# main.net
KiCad netlist of a schematic drawn in Altium Designer
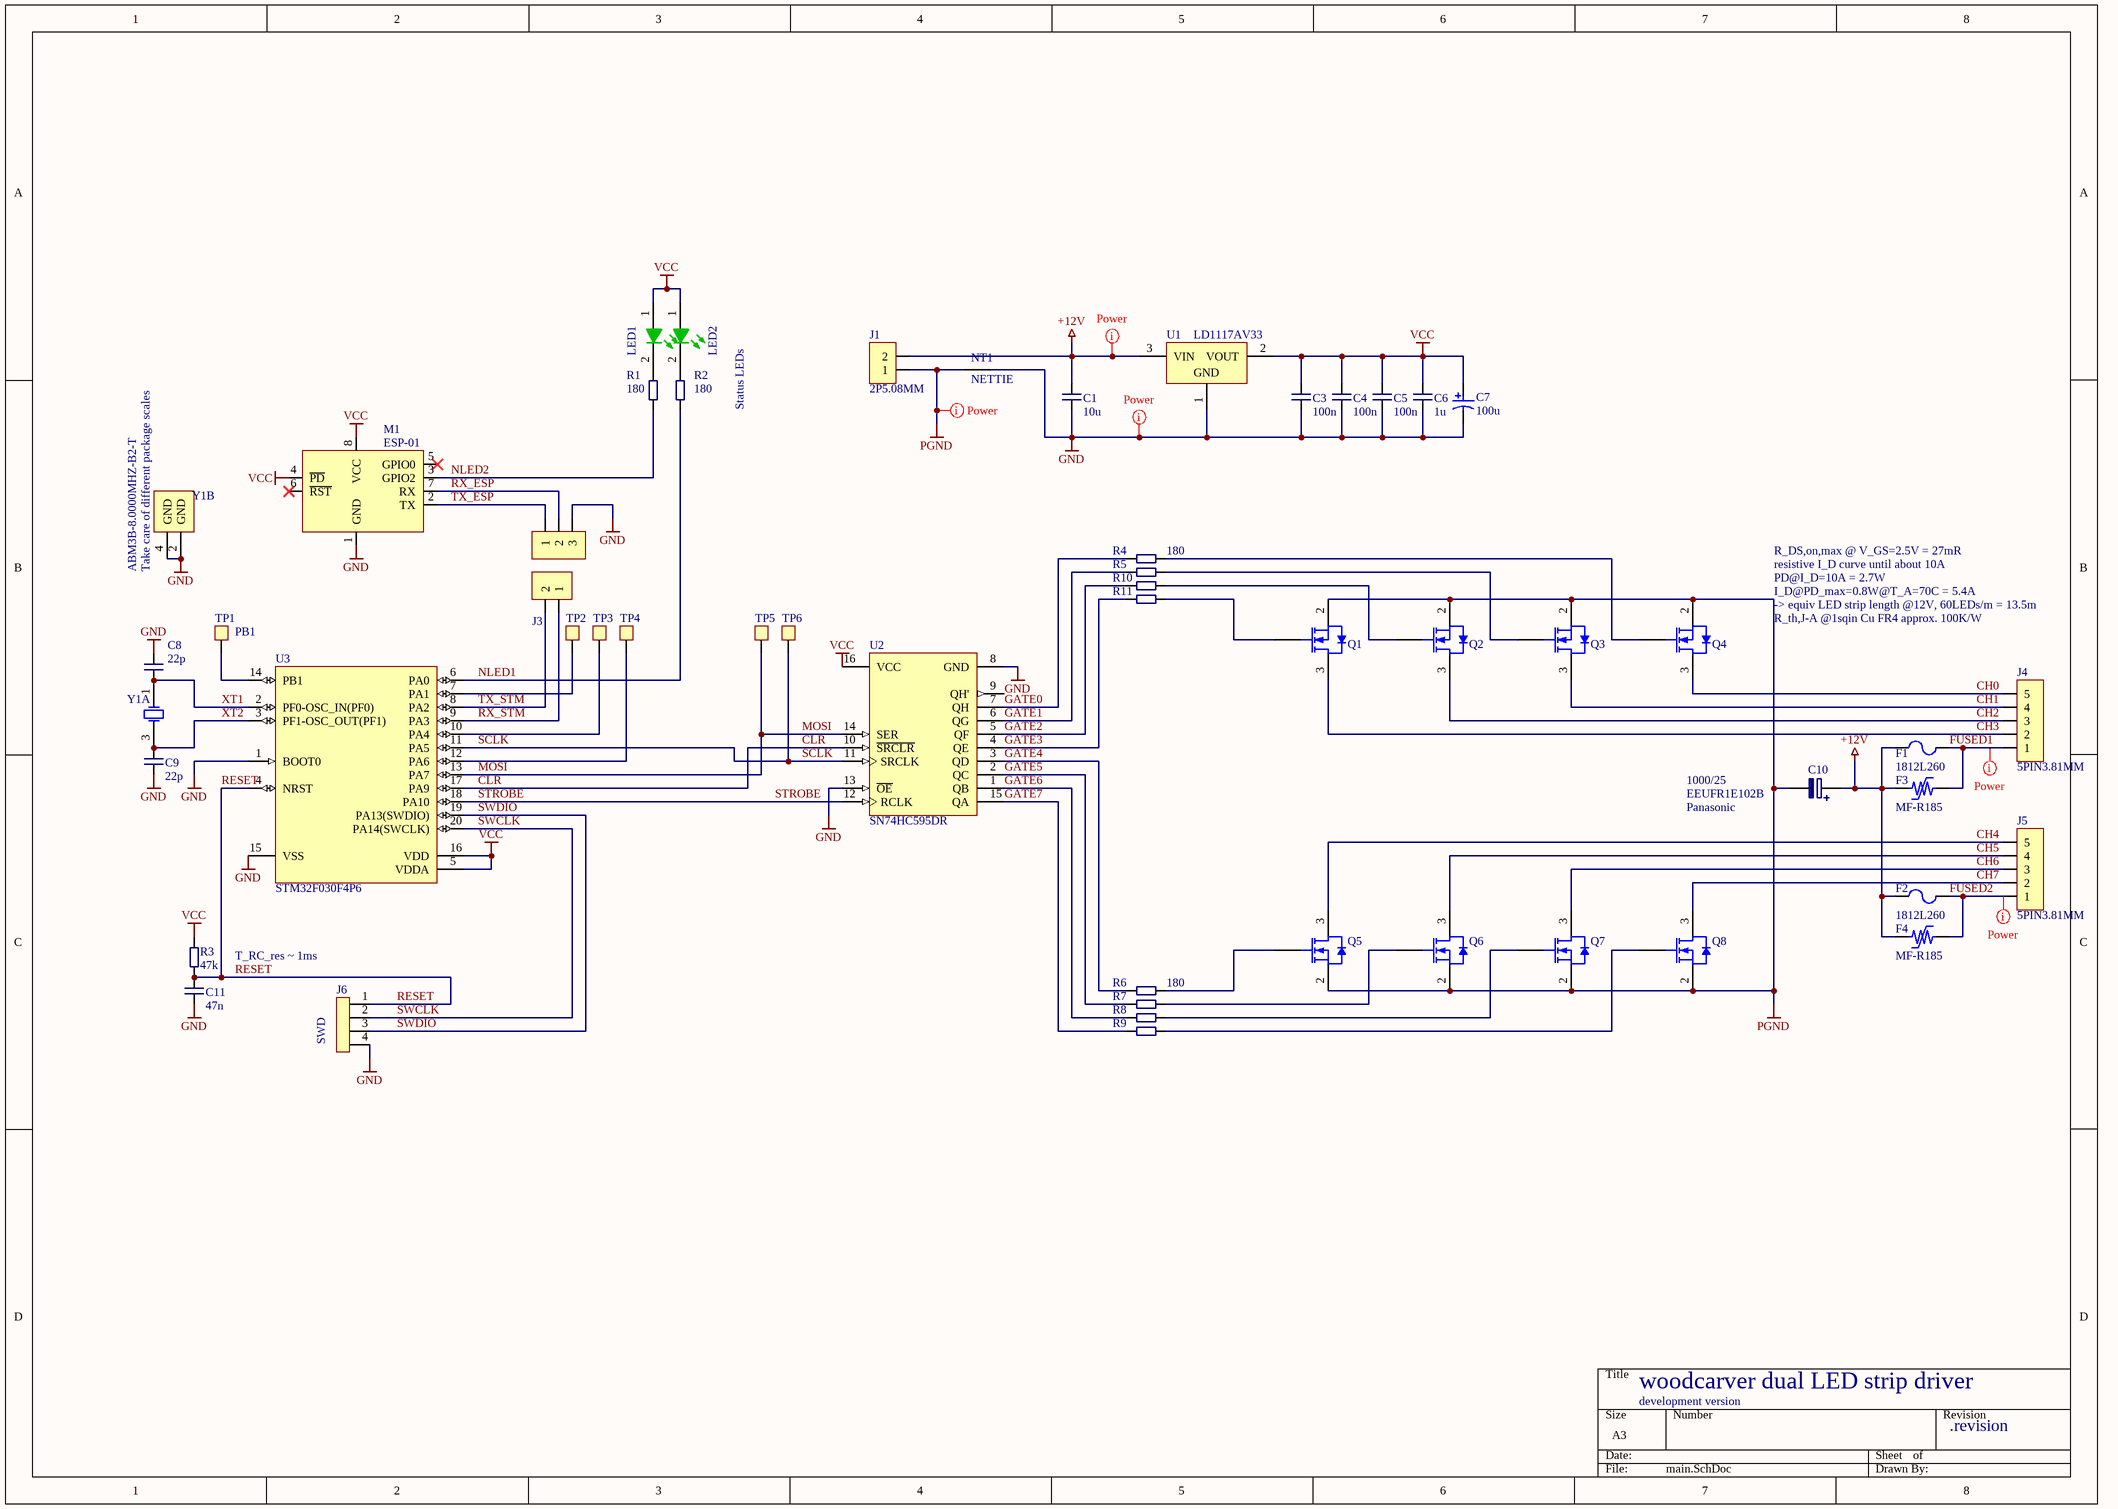
[diagram p0: main.SchDoc]

(export (version "E")
  (design (tool "Eeschema 10.0.6"))
  (components
    (comp (ref "C1")
      (value "10u")
      (footprint "6-0805_M")
      (description "Capacitor")
      (libsource (lib "components") (part "C"))
    )
    (comp (ref "C3")
      (value "100n")
      (footprint "J1-0603")
      (description "Capacitor")
      (libsource (lib "components") (part "C"))
    )
    (comp (ref "C4")
      (value "100n")
      (footprint "J1-0603")
      (description "Capacitor")
      (libsource (lib "components") (part "C"))
    )
    (comp (ref "C5")
      (value "100n")
      (footprint "J1-0603")
      (description "Capacitor")
      (libsource (lib "components") (part "C"))
    )
    (comp (ref "C6")
      (value "1u")
      (footprint "6-0805_M")
      (description "Capacitor")
      (libsource (lib "components") (part "C"))
    )
    (comp (ref "C7")
      (value "100u")
      (footprint "FHTE-8-AA07-2_N")
      (fields
        (field (name "MANUFACTURER") "Fenghuang Technology")
        (field (name "PARTNUMBER") "8471LCJAA07WPN081T")
        (field (name "TOLERANCE") "+/- 5%")
      )
      (libsource (lib "Altium Content Vault") (part "FHTE-CAP-P-2"))
    )
    (comp (ref "C8")
      (value "22p")
      (footprint "J1-0603")
      (description "Capacitor")
      (libsource (lib "components") (part "C"))
    )
    (comp (ref "C9")
      (value "22p")
      (footprint "J1-0603")
      (description "Capacitor")
      (libsource (lib "components") (part "C"))
    )
    (comp (ref "C10")
      (value "1000/25")
      (footprint "ELKO_10MM_RM5_SIDE_25MM")
      (fields (field (name "MFG PART NO") "EEUFR1E102B") (field (name "MFG") "Panasonic"))
      (libsource (lib "components") (part "ELKO"))
    )
    (comp (ref "C11")
      (value "47n")
      (footprint "J1-0603")
      (description "Capacitor")
      (libsource (lib "components") (part "C"))
    )
    (comp (ref "F1")
      (value "1812L260")
      (footprint "LFUS-FUSE1812-71_V")
      (description "Resettable PTC, 1812, 1.5 A Ihold, 3.0 A Itrip")
      (fields (field (name "PARTNUMBER") "1812L150ZR"))
      (libsource (lib "Altium Content Vault") (part "LFUS-FUSE-2"))
    )
    (comp (ref "F2")
      (value "1812L260")
      (footprint "LFUS-FUSE1812-71_V")
      (description "Resettable PTC, 1812, 1.5 A Ihold, 3.0 A Itrip")
      (fields (field (name "PARTNUMBER") "1812L150ZR"))
      (libsource (lib "Altium Content Vault") (part "LFUS-FUSE-2"))
    )
    (comp (ref "F3")
      (value "MF-R185")
      (footprint "BOUR-MF-R185")
      (description "PTC Resettable Fuse, 30 V, 40 A, -40 to 85 degC, 2-Pin THD, RoHS, Bulk")
      (fields (field (name "MANUFACTURER") "Bourns"))
      (libsource (lib "Altium Content Vault") (part "PPTC-2"))
    )
    (comp (ref "F4")
      (value "MF-R185")
      (footprint "BOUR-MF-R185")
      (description "PTC Resettable Fuse, 30 V, 40 A, -40 to 85 degC, 2-Pin THD, RoHS, Bulk")
      (fields (field (name "MANUFACTURER") "Bourns"))
      (libsource (lib "Altium Content Vault") (part "PPTC-2"))
    )
    (comp (ref "J1")
      (value "2P5.08MM")
      (footprint "HEADER_2PIN_RM5.08MM_PLUGGABLE")
      (description "Pluggable Header 2 Pin RM 5.08mm ~15A")
      (libsource (lib "components") (part "PHD2P5.08RM"))
    )
    (comp (ref "J2")
      (value "PINHD_1x3_2.54MM")
      (footprint "PINHD_3X1_2.54MM")
      (description "Pin Header 1 row 3 pin RM 2.54mm")
      (libsource (lib "components") (part "PINHD1X3"))
    )
    (comp (ref "J3")
      (value "PINHD_1x2_2.54MM")
      (footprint "PINHD_2X1_2.54MM")
      (description "Pin Header 1 row 2 pin RM 2.54mm")
      (libsource (lib "components") (part "PINHD1X2"))
    )
    (comp (ref "J4")
      (value "5PIN3.81MM")
      (footprint "HEADER_5PIN_RM3.81MM_PLUGGABLE")
      (description "Pluggable Header 5 Pin RM 3.81mm ~8A")
      (libsource (lib "components") (part "PHD5P3.81RM"))
    )
    (comp (ref "J5")
      (value "5PIN3.81MM")
      (footprint "HEADER_5PIN_RM3.81MM_PLUGGABLE")
      (description "Pluggable Header 5 Pin RM 3.81mm ~8A")
      (libsource (lib "components") (part "PHD5P3.81RM"))
    )
    (comp (ref "J6")
      (value "SWD")
      (footprint "PINHD_4X1_2.54MM")
      (description "Pin Header 4x1 pin")
      (libsource (lib "components") (part "PH_4x1"))
    )
    (comp (ref "LED1")
      (value "KP-1608MGC")
      (footprint "KING-0603LED_GREEN_V")
      (description "LED, SMT, 0603(1608), 1.1mm thickness, Green")
      (fields (field (name "MANUFACTURER") "Kingbright"))
      (libsource (lib "components") (part "CMP-0404-00001-1"))
    )
    (comp (ref "LED2")
      (value "KP-1608MGC")
      (footprint "KING-0603LED_GREEN_V")
      (description "LED, SMT, 0603(1608), 1.1mm thickness, Green")
      (fields (field (name "MANUFACTURER") "Kingbright"))
      (libsource (lib "components") (part "CMP-0404-00001-1"))
    )
    (comp (ref "M1")
      (value "ESP-01")
      (footprint "ESP01")
      (description "ESP-01 ESP8266 Wifi Module")
      (libsource (lib "components") (part "ESP01"))
    )
    (comp (ref "NT1") (value "NETTIE") (footprint "NETTIE") (libsource (lib "components") (part "NETTIE")))
    (comp (ref "Q1")
      (value "IRLML6244TRPbF")
      (footprint "ONSC-SOT-23-3-318-08_V")
      (description "Power MOSFET, 500 mA, 60 V, N-Channel, 3-Pin SOT-23, Pb-Free, Tape and Reel")
      (fields (field (name "MANUFACTURER") "On Semiconductor") (field (name "PARTNUMBER") "NVBF170LT1G"))
      (libsource (lib "Altium Content Vault") (part "ONSC-NMOS-G1S2D3-3"))
    )
    (comp (ref "Q2")
      (value "IRLML6244TRPbF")
      (footprint "ONSC-SOT-23-3-318-08_V")
      (description "Power MOSFET, 500 mA, 60 V, N-Channel, 3-Pin SOT-23, Pb-Free, Tape and Reel")
      (fields (field (name "MANUFACTURER") "On Semiconductor") (field (name "PARTNUMBER") "NVBF170LT1G"))
      (libsource (lib "Altium Content Vault") (part "ONSC-NMOS-G1S2D3-3"))
    )
    (comp (ref "Q3")
      (value "IRLML6244TRPbF")
      (footprint "ONSC-SOT-23-3-318-08_V")
      (description "Power MOSFET, 500 mA, 60 V, N-Channel, 3-Pin SOT-23, Pb-Free, Tape and Reel")
      (fields (field (name "MANUFACTURER") "On Semiconductor") (field (name "PARTNUMBER") "NVBF170LT1G"))
      (libsource (lib "Altium Content Vault") (part "ONSC-NMOS-G1S2D3-3"))
    )
    (comp (ref "Q4")
      (value "IRLML6244TRPbF")
      (footprint "ONSC-SOT-23-3-318-08_V")
      (description "Power MOSFET, 500 mA, 60 V, N-Channel, 3-Pin SOT-23, Pb-Free, Tape and Reel")
      (fields (field (name "MANUFACTURER") "On Semiconductor") (field (name "PARTNUMBER") "NVBF170LT1G"))
      (libsource (lib "Altium Content Vault") (part "ONSC-NMOS-G1S2D3-3"))
    )
    (comp (ref "Q5")
      (value "IRLML6244TRPbF")
      (footprint "ONSC-SOT-23-3-318-08_V")
      (description "Power MOSFET, 500 mA, 60 V, N-Channel, 3-Pin SOT-23, Pb-Free, Tape and Reel")
      (fields (field (name "MANUFACTURER") "On Semiconductor") (field (name "PARTNUMBER") "NVBF170LT1G"))
      (libsource (lib "Altium Content Vault") (part "ONSC-NMOS-G1S2D3-3"))
    )
    (comp (ref "Q6")
      (value "IRLML6244TRPbF")
      (footprint "ONSC-SOT-23-3-318-08_V")
      (description "Power MOSFET, 500 mA, 60 V, N-Channel, 3-Pin SOT-23, Pb-Free, Tape and Reel")
      (fields (field (name "MANUFACTURER") "On Semiconductor") (field (name "PARTNUMBER") "NVBF170LT1G"))
      (libsource (lib "Altium Content Vault") (part "ONSC-NMOS-G1S2D3-3"))
    )
    (comp (ref "Q7")
      (value "IRLML6244TRPbF")
      (footprint "ONSC-SOT-23-3-318-08_V")
      (description "Power MOSFET, 500 mA, 60 V, N-Channel, 3-Pin SOT-23, Pb-Free, Tape and Reel")
      (fields (field (name "MANUFACTURER") "On Semiconductor") (field (name "PARTNUMBER") "NVBF170LT1G"))
      (libsource (lib "Altium Content Vault") (part "ONSC-NMOS-G1S2D3-3"))
    )
    (comp (ref "Q8")
      (value "IRLML6244TRPbF")
      (footprint "ONSC-SOT-23-3-318-08_V")
      (description "Power MOSFET, 500 mA, 60 V, N-Channel, 3-Pin SOT-23, Pb-Free, Tape and Reel")
      (fields (field (name "MANUFACTURER") "On Semiconductor") (field (name "PARTNUMBER") "NVBF170LT1G"))
      (libsource (lib "Altium Content Vault") (part "ONSC-NMOS-G1S2D3-3"))
    )
    (comp (ref "R1")
      (value "180")
      (footprint "J1-0603")
      (description "Resistor")
      (libsource (lib "components") (part "R"))
    )
    (comp (ref "R2")
      (value "180")
      (footprint "J1-0603")
      (description "Resistor")
      (libsource (lib "components") (part "R"))
    )
    (comp (ref "R3")
      (value "47k")
      (footprint "J1-0603")
      (description "Resistor")
      (libsource (lib "components") (part "R"))
    )
    (comp (ref "R4")
      (value "180")
      (footprint "J1-0603")
      (description "Resistor")
      (libsource (lib "components") (part "R"))
    )
    (comp (ref "R5")
      (value "180")
      (footprint "J1-0603")
      (description "Resistor")
      (libsource (lib "components") (part "R"))
    )
    (comp (ref "R6")
      (value "180")
      (footprint "J1-0603")
      (description "Resistor")
      (libsource (lib "components") (part "R"))
    )
    (comp (ref "R7")
      (value "180")
      (footprint "J1-0603")
      (description "Resistor")
      (libsource (lib "components") (part "R"))
    )
    (comp (ref "R8")
      (value "180")
      (footprint "J1-0603")
      (description "Resistor")
      (libsource (lib "components") (part "R"))
    )
    (comp (ref "R9")
      (value "180")
      (footprint "J1-0603")
      (description "Resistor")
      (libsource (lib "components") (part "R"))
    )
    (comp (ref "R10")
      (value "180")
      (footprint "J1-0603")
      (description "Resistor")
      (libsource (lib "components") (part "R"))
    )
    (comp (ref "R11")
      (value "180")
      (footprint "J1-0603")
      (description "Resistor")
      (libsource (lib "components") (part "R"))
    )
    (comp (ref "TP1")
      (value "PB1")
      (footprint "TESTPOINT_2mm")
      (description "Testpoint")
      (libsource (lib "components") (part "TESTPOINT"))
    )
    (comp (ref "TP2")
      (value "PA1")
      (footprint "TESTPOINT_2mm")
      (description "Testpoint")
      (libsource (lib "components") (part "TESTPOINT"))
    )
    (comp (ref "TP3")
      (value "PA4")
      (footprint "TESTPOINT_2mm")
      (description "Testpoint")
      (libsource (lib "components") (part "TESTPOINT"))
    )
    (comp (ref "TP4")
      (value "PA6")
      (footprint "TESTPOINT_2mm")
      (description "Testpoint")
      (libsource (lib "components") (part "TESTPOINT"))
    )
    (comp (ref "TP5")
      (value "PA6")
      (footprint "TESTPOINT_2mm")
      (description "Testpoint")
      (libsource (lib "components") (part "TESTPOINT"))
    )
    (comp (ref "TP6")
      (value "PA6")
      (footprint "TESTPOINT_2mm")
      (description "Testpoint")
      (libsource (lib "components") (part "TESTPOINT"))
    )
    (comp (ref "U1")
      (value "LD1117AV33")
      (footprint "TO220")
      (description "1A, Low Drop Positive Voltage Regulator, 3.3V, 3-Pin TO-220")
      (libsource (lib "Altium Content Vault") (part "PM-REG-LD1117V-SIL3"))
    )
    (comp (ref "U2")
      (value "SN74HC595DR")
      (footprint "D0016A_M")
      (description "8-Bit Shift Registers With 3-State Output Registers, D0016A, LARGE T&R")
      (fields
        (field (name "GENERIC PART NUMBER") "SN74HC595")
        (field (name "MANUFACTURER") "Texas Instruments")
      )
      (libsource (lib "Altium Content Vault") (part "CMP-0780-00037-3"))
    )
    (comp (ref "U3")
      (value "STM32F030F4P6")
      (footprint "STM-TSSOP20_L")
      (libsource (lib "Altium Content Vault") (part "MC-ARM-STM32F030-IL20"))
    )
    (comp (ref "Y1")
      (value "ABM3B-8.0000MHZ-B2-T")
      (footprint "XTAL_MJ_5x3.2")
      (description "Crystal, SMD, 25.000000MHz Stab=50ppm 18.0pF")
      (fields
        (field (name "MANUFACTURER") "Abracon")
        (field (name "PARTNUMBER") "ABM3B-25.000MHZ-B2-T")
        (field (name "NOTE") "Take care of different package scales")
      )
      (libsource (lib "components") (part "ABRA-ABM3B-4"))
    )
  )
  (nets
    (net (code "1") (name "+12V") (class "Default")
      (node (ref "C1") (pin "1") (pinfunction "1_1") (pintype "passive"))
      (node (ref "C10") (pin "1") (pinfunction "1_1") (pintype "passive"))
      (node (ref "F1") (pin "1") (pinfunction "1_1") (pintype "passive"))
      (node (ref "F2") (pin "1") (pinfunction "1_1") (pintype "passive"))
      (node (ref "F3") (pin "1") (pinfunction "1_1") (pintype "passive"))
      (node (ref "F4") (pin "1") (pinfunction "1_1") (pintype "passive"))
      (node (ref "J1") (pin "2") (pinfunction "2_2") (pintype "passive"))
      (node (ref "U1") (pin "3") (pinfunction "VIN_3") (pintype "power_in"))
    )
    (net (code "2") (name "/CH0") (class "Default")
      (node (ref "J4") (pin "5") (pinfunction "5_5") (pintype "passive"))
      (node (ref "Q4") (pin "3") (pinfunction "D_3") (pintype "passive"))
    )
    (net (code "3") (name "/CH1") (class "Default")
      (node (ref "J4") (pin "4") (pinfunction "4_4") (pintype "passive"))
      (node (ref "Q3") (pin "3") (pinfunction "D_3") (pintype "passive"))
    )
    (net (code "4") (name "/CH2") (class "Default")
      (node (ref "J4") (pin "3") (pinfunction "3_3") (pintype "passive"))
      (node (ref "Q2") (pin "3") (pinfunction "D_3") (pintype "passive"))
    )
    (net (code "5") (name "/CH3") (class "Default")
      (node (ref "J4") (pin "2") (pinfunction "2_2") (pintype "passive"))
      (node (ref "Q1") (pin "3") (pinfunction "D_3") (pintype "passive"))
    )
    (net (code "6") (name "/CH4") (class "Default")
      (node (ref "J5") (pin "5") (pinfunction "5_5") (pintype "passive"))
      (node (ref "Q5") (pin "3") (pinfunction "D_3") (pintype "passive"))
    )
    (net (code "7") (name "/CH5") (class "Default")
      (node (ref "J5") (pin "4") (pinfunction "4_4") (pintype "passive"))
      (node (ref "Q6") (pin "3") (pinfunction "D_3") (pintype "passive"))
    )
    (net (code "8") (name "/CH6") (class "Default")
      (node (ref "J5") (pin "3") (pinfunction "3_3") (pintype "passive"))
      (node (ref "Q7") (pin "3") (pinfunction "D_3") (pintype "passive"))
    )
    (net (code "9") (name "/CH7") (class "Default")
      (node (ref "J5") (pin "2") (pinfunction "2_2") (pintype "passive"))
      (node (ref "Q8") (pin "3") (pinfunction "D_3") (pintype "passive"))
    )
    (net (code "10") (name "/CLR") (class "Default")
      (node (ref "U2") (pin "10") (pinfunction "~{SRCLR}_10") (pintype "input"))
      (node (ref "U3") (pin "17") (pinfunction "PA9_17") (pintype "bidirectional"))
    )
    (net (code "11") (name "/FUSED1") (class "Default")
      (node (ref "F1") (pin "2") (pinfunction "2_2") (pintype "passive"))
      (node (ref "F3") (pin "2") (pinfunction "2_2") (pintype "passive"))
      (node (ref "J4") (pin "1") (pinfunction "1_1") (pintype "passive"))
    )
    (net (code "12") (name "/FUSED2") (class "Default")
      (node (ref "F2") (pin "2") (pinfunction "2_2") (pintype "passive"))
      (node (ref "F4") (pin "2") (pinfunction "2_2") (pintype "passive"))
      (node (ref "J5") (pin "1") (pinfunction "1_1") (pintype "passive"))
    )
    (net (code "13") (name "/GATE0") (class "Default")
      (node (ref "R4") (pin "2") (pinfunction "2_2") (pintype "passive"))
      (node (ref "U2") (pin "7") (pinfunction "QH_7") (pintype "tri_state"))
    )
    (net (code "14") (name "/GATE1") (class "Default")
      (node (ref "R5") (pin "2") (pinfunction "2_2") (pintype "passive"))
      (node (ref "U2") (pin "6") (pinfunction "QG_6") (pintype "tri_state"))
    )
    (net (code "15") (name "/GATE2") (class "Default")
      (node (ref "R10") (pin "2") (pinfunction "2_2") (pintype "passive"))
      (node (ref "U2") (pin "5") (pinfunction "QF_5") (pintype "tri_state"))
    )
    (net (code "16") (name "/GATE3") (class "Default")
      (node (ref "R11") (pin "2") (pinfunction "2_2") (pintype "passive"))
      (node (ref "U2") (pin "4") (pinfunction "QE_4") (pintype "tri_state"))
    )
    (net (code "17") (name "/GATE4") (class "Default")
      (node (ref "R6") (pin "2") (pinfunction "2_2") (pintype "passive"))
      (node (ref "U2") (pin "3") (pinfunction "QD_3") (pintype "tri_state"))
    )
    (net (code "18") (name "/GATE5") (class "Default")
      (node (ref "R7") (pin "2") (pinfunction "2_2") (pintype "passive"))
      (node (ref "U2") (pin "2") (pinfunction "QC_2") (pintype "tri_state"))
    )
    (net (code "19") (name "/GATE6") (class "Default")
      (node (ref "R8") (pin "2") (pinfunction "2_2") (pintype "passive"))
      (node (ref "U2") (pin "1") (pinfunction "QB_1") (pintype "tri_state"))
    )
    (net (code "20") (name "/GATE7") (class "Default")
      (node (ref "R9") (pin "2") (pinfunction "2_2") (pintype "passive"))
      (node (ref "U2") (pin "15") (pinfunction "QA_15") (pintype "tri_state"))
    )
    (net (code "21") (name "/MOSI") (class "Default")
      (node (ref "TP5") (pin "1") (pinfunction "1_1") (pintype "passive"))
      (node (ref "U2") (pin "14") (pinfunction "SER_14") (pintype "input"))
      (node (ref "U3") (pin "13") (pinfunction "PA7_13") (pintype "bidirectional"))
    )
    (net (code "22") (name "/NLED1") (class "Default")
      (node (ref "R2") (pin "1") (pinfunction "1_1") (pintype "passive"))
      (node (ref "U3") (pin "6") (pinfunction "PA0_6") (pintype "bidirectional"))
    )
    (net (code "23") (name "/NLED2") (class "Default")
      (node (ref "M1") (pin "3") (pinfunction "GPIO2_3") (pintype "passive"))
      (node (ref "R1") (pin "1") (pinfunction "1_1") (pintype "passive"))
    )
    (net (code "24") (name "/RESET") (class "Default")
      (node (ref "C11") (pin "1") (pinfunction "1_1") (pintype "passive"))
      (node (ref "J6") (pin "1") (pinfunction "1_1") (pintype "passive"))
      (node (ref "R3") (pin "1") (pinfunction "1_1") (pintype "passive"))
      (node (ref "U3") (pin "4") (pinfunction "NRST_4") (pintype "bidirectional"))
    )
    (net (code "25") (name "/RX_ESP") (class "Default")
      (node (ref "J2") (pin "2") (pinfunction "2_2") (pintype "passive"))
      (node (ref "M1") (pin "7") (pinfunction "RX_7") (pintype "passive"))
    )
    (net (code "26") (name "/RX_STM") (class "Default")
      (node (ref "J3") (pin "1") (pinfunction "1_1") (pintype "passive"))
      (node (ref "U3") (pin "9") (pinfunction "PA3_9") (pintype "bidirectional"))
    )
    (net (code "27") (name "/SCLK") (class "Default")
      (node (ref "TP6") (pin "1") (pinfunction "1_1") (pintype "passive"))
      (node (ref "U2") (pin "11") (pinfunction "SRCLK_11") (pintype "input"))
      (node (ref "U3") (pin "11") (pinfunction "PA5_11") (pintype "bidirectional"))
    )
    (net (code "28") (name "/STROBE") (class "Default")
      (node (ref "U2") (pin "12") (pinfunction "RCLK_12") (pintype "input"))
      (node (ref "U3") (pin "18") (pinfunction "PA10_18") (pintype "bidirectional"))
    )
    (net (code "29") (name "/SWCLK") (class "Default")
      (node (ref "J6") (pin "2") (pinfunction "2_2") (pintype "passive"))
      (node (ref "U3") (pin "20") (pinfunction "PA14(SWCLK)_20") (pintype "bidirectional"))
    )
    (net (code "30") (name "/SWDIO") (class "Default")
      (node (ref "J6") (pin "3") (pinfunction "3_3") (pintype "passive"))
      (node (ref "U3") (pin "19") (pinfunction "PA13(SWDIO)_19") (pintype "bidirectional"))
    )
    (net (code "31") (name "/TX_ESP") (class "Default")
      (node (ref "J2") (pin "1") (pinfunction "1_1") (pintype "passive"))
      (node (ref "M1") (pin "2") (pinfunction "TX_2") (pintype "passive"))
    )
    (net (code "32") (name "/TX_STM") (class "Default")
      (node (ref "J3") (pin "2") (pinfunction "2_2") (pintype "passive"))
      (node (ref "U3") (pin "8") (pinfunction "PA2_8") (pintype "bidirectional"))
    )
    (net (code "33") (name "/XT1") (class "Default")
      (node (ref "C8") (pin "2") (pinfunction "2_2") (pintype "passive"))
      (node (ref "U3") (pin "2") (pinfunction "PF0-OSC_IN(PF0)_2") (pintype "bidirectional"))
      (node (ref "Y1") (pin "1") (pinfunction "X1_1") (pintype "passive"))
    )
    (net (code "34") (name "/XT2") (class "Default")
      (node (ref "C9") (pin "1") (pinfunction "1_1") (pintype "passive"))
      (node (ref "U3") (pin "3") (pinfunction "PF1-OSC_OUT(PF1)_3") (pintype "bidirectional"))
      (node (ref "Y1") (pin "3") (pinfunction "X2_3") (pintype "passive"))
    )
    (net (code "35") (name "GND") (class "Default")
      (node (ref "C1") (pin "2") (pinfunction "2_2") (pintype "passive"))
      (node (ref "C11") (pin "2") (pinfunction "2_2") (pintype "passive"))
      (node (ref "C3") (pin "2") (pinfunction "2_2") (pintype "passive"))
      (node (ref "C4") (pin "2") (pinfunction "2_2") (pintype "passive"))
      (node (ref "C5") (pin "2") (pinfunction "2_2") (pintype "passive"))
      (node (ref "C6") (pin "2") (pinfunction "2_2") (pintype "passive"))
      (node (ref "C7") (pin "2") (pinfunction "2_2") (pintype "passive"))
      (node (ref "C8") (pin "1") (pinfunction "1_1") (pintype "passive"))
      (node (ref "C9") (pin "2") (pinfunction "2_2") (pintype "passive"))
      (node (ref "J2") (pin "3") (pinfunction "3_3") (pintype "passive"))
      (node (ref "J6") (pin "4") (pinfunction "4_4") (pintype "passive"))
      (node (ref "M1") (pin "1") (pinfunction "GND_1") (pintype "passive"))
      (node (ref "NT1") (pin "2") (pinfunction "2_2") (pintype "passive"))
      (node (ref "U1") (pin "1") (pinfunction "GND_1") (pintype "power_in"))
      (node (ref "U2") (pin "13") (pinfunction "~{OE}_13") (pintype "input"))
      (node (ref "U2") (pin "8") (pinfunction "GND_8") (pintype "power_in"))
      (node (ref "U3") (pin "1") (pinfunction "BOOT0_1") (pintype "input"))
      (node (ref "U3") (pin "15") (pinfunction "VSS_15") (pintype "power_in"))
      (node (ref "Y1") (pin "2") (pinfunction "GND_2") (pintype "power_in"))
      (node (ref "Y1") (pin "4") (pinfunction "GND_4") (pintype "power_in"))
    )
    (net (code "36") (name "Net-(LED1-K)") (class "Default")
      (node (ref "LED1") (pin "2") (pinfunction "K_2") (pintype "passive"))
      (node (ref "R1") (pin "2") (pinfunction "2_2") (pintype "passive"))
    )
    (net (code "37") (name "Net-(LED2-K)") (class "Default")
      (node (ref "LED2") (pin "2") (pinfunction "K_2") (pintype "passive"))
      (node (ref "R2") (pin "2") (pinfunction "2_2") (pintype "passive"))
    )
    (net (code "38") (name "Net-(Q1-G)") (class "Default")
      (node (ref "Q1") (pin "1") (pinfunction "G_1") (pintype "passive"))
      (node (ref "R11") (pin "1") (pinfunction "1_1") (pintype "passive"))
    )
    (net (code "39") (name "Net-(Q2-G)") (class "Default")
      (node (ref "Q2") (pin "1") (pinfunction "G_1") (pintype "passive"))
      (node (ref "R10") (pin "1") (pinfunction "1_1") (pintype "passive"))
    )
    (net (code "40") (name "Net-(Q3-G)") (class "Default")
      (node (ref "Q3") (pin "1") (pinfunction "G_1") (pintype "passive"))
      (node (ref "R5") (pin "1") (pinfunction "1_1") (pintype "passive"))
    )
    (net (code "41") (name "Net-(Q4-G)") (class "Default")
      (node (ref "Q4") (pin "1") (pinfunction "G_1") (pintype "passive"))
      (node (ref "R4") (pin "1") (pinfunction "1_1") (pintype "passive"))
    )
    (net (code "42") (name "Net-(Q5-G)") (class "Default")
      (node (ref "Q5") (pin "1") (pinfunction "G_1") (pintype "passive"))
      (node (ref "R6") (pin "1") (pinfunction "1_1") (pintype "passive"))
    )
    (net (code "43") (name "Net-(Q6-G)") (class "Default")
      (node (ref "Q6") (pin "1") (pinfunction "G_1") (pintype "passive"))
      (node (ref "R7") (pin "1") (pinfunction "1_1") (pintype "passive"))
    )
    (net (code "44") (name "Net-(Q7-G)") (class "Default")
      (node (ref "Q7") (pin "1") (pinfunction "G_1") (pintype "passive"))
      (node (ref "R8") (pin "1") (pinfunction "1_1") (pintype "passive"))
    )
    (net (code "45") (name "Net-(Q8-G)") (class "Default")
      (node (ref "Q8") (pin "1") (pinfunction "G_1") (pintype "passive"))
      (node (ref "R9") (pin "1") (pinfunction "1_1") (pintype "passive"))
    )
    (net (code "46") (name "Net-(U3-PA1)") (class "Default")
      (node (ref "TP2") (pin "1") (pinfunction "1_1") (pintype "passive"))
      (node (ref "U3") (pin "7") (pinfunction "PA1_7") (pintype "bidirectional"))
    )
    (net (code "47") (name "Net-(U3-PA4)") (class "Default")
      (node (ref "TP3") (pin "1") (pinfunction "1_1") (pintype "passive"))
      (node (ref "U3") (pin "10") (pinfunction "PA4_10") (pintype "bidirectional"))
    )
    (net (code "48") (name "Net-(U3-PA6)") (class "Default")
      (node (ref "TP4") (pin "1") (pinfunction "1_1") (pintype "passive"))
      (node (ref "U3") (pin "12") (pinfunction "PA6_12") (pintype "bidirectional"))
    )
    (net (code "49") (name "Net-(U3-PB1)") (class "Default")
      (node (ref "TP1") (pin "1") (pinfunction "1_1") (pintype "passive"))
      (node (ref "U3") (pin "14") (pinfunction "PB1_14") (pintype "bidirectional"))
    )
    (net (code "50") (name "PGND") (class "Default")
      (node (ref "C10") (pin "2") (pinfunction "2_2") (pintype "passive"))
      (node (ref "J1") (pin "1") (pinfunction "1_1") (pintype "passive"))
      (node (ref "NT1") (pin "1") (pinfunction "1_1") (pintype "passive"))
      (node (ref "Q1") (pin "2") (pinfunction "S_2") (pintype "passive"))
      (node (ref "Q2") (pin "2") (pinfunction "S_2") (pintype "passive"))
      (node (ref "Q3") (pin "2") (pinfunction "S_2") (pintype "passive"))
      (node (ref "Q4") (pin "2") (pinfunction "S_2") (pintype "passive"))
      (node (ref "Q5") (pin "2") (pinfunction "S_2") (pintype "passive"))
      (node (ref "Q6") (pin "2") (pinfunction "S_2") (pintype "passive"))
      (node (ref "Q7") (pin "2") (pinfunction "S_2") (pintype "passive"))
      (node (ref "Q8") (pin "2") (pinfunction "S_2") (pintype "passive"))
    )
    (net (code "51") (name "VCC") (class "Default")
      (node (ref "C3") (pin "1") (pinfunction "1_1") (pintype "passive"))
      (node (ref "C4") (pin "1") (pinfunction "1_1") (pintype "passive"))
      (node (ref "C5") (pin "1") (pinfunction "1_1") (pintype "passive"))
      (node (ref "C6") (pin "1") (pinfunction "1_1") (pintype "passive"))
      (node (ref "C7") (pin "1") (pinfunction "1_1") (pintype "passive"))
      (node (ref "LED1") (pin "1") (pinfunction "A_1") (pintype "passive"))
      (node (ref "LED2") (pin "1") (pinfunction "A_1") (pintype "passive"))
      (node (ref "M1") (pin "4") (pinfunction "~{PD}_4") (pintype "passive"))
      (node (ref "M1") (pin "8") (pinfunction "VCC_8") (pintype "passive"))
      (node (ref "R3") (pin "2") (pinfunction "2_2") (pintype "passive"))
      (node (ref "U1") (pin "2") (pinfunction "VOUT_2") (pintype "power_in"))
      (node (ref "U2") (pin "16") (pinfunction "VCC_16") (pintype "power_in"))
      (node (ref "U3") (pin "16") (pinfunction "VDD_16") (pintype "power_in"))
      (node (ref "U3") (pin "5") (pinfunction "VDDA_5") (pintype "power_in"))
    )
    (net (code "52") (name "unconnected-(M1-GPIO0-Pad5)") (class "Default")
      (node (ref "M1") (pin "5") (pinfunction "GPIO0_5") (pintype "passive+no_connect"))
    )
    (net (code "53") (name "unconnected-(M1-~{RST}-Pad6)") (class "Default")
      (node (ref "M1") (pin "6") (pinfunction "~{RST}_6") (pintype "passive+no_connect"))
    )
    (net (code "54") (name "unconnected-(U2-QH'-Pad9)") (class "Default")
      (node (ref "U2") (pin "9") (pinfunction "QH'_9") (pintype "output"))
    )
  )
)
